# Power_Input.net
KiCad netlist of a schematic drawn in Altium Designer
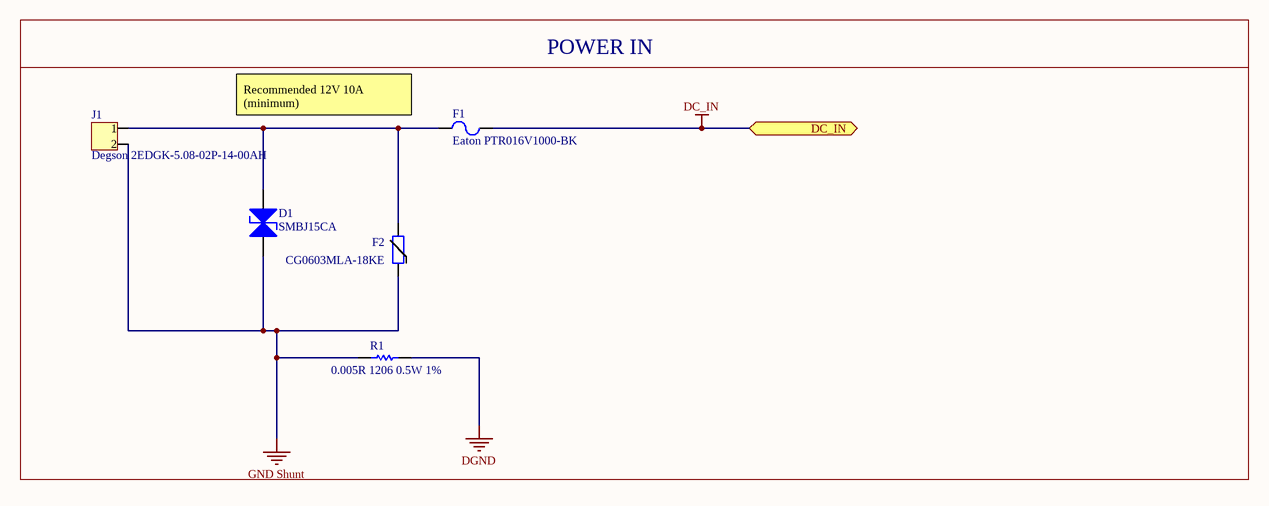
[diagram p0: Power_Input.SchDoc]

(export (version "E")
  (design (tool "Eeschema 10.0.6"))
  (components
    (comp (ref "D1")
      (value "SMBJ15CA")
      (footprint "PCB-acsqsz06h0bi34fqghyj-1")
      (description "SMBJ15 Series 24.4 V 600 W Bi-Directional Transient Voltage Suppressor-DO-214AA")
      (libsource (lib "CommunityVault") (part "SYM-f09b39914f642f5c-1"))
    )
    (comp (ref "F1")
      (value "Eaton PTR016V1000-BK")
      (footprint "PCB-m5opblue4hjll7k5rrhf-1")
      (description "PTC Resettable Fuse 10A(hold) 17A(trip) 16VDC 100A 3.6W 6s 0.004Ohm Radial 16.5 X 3.1 X 25.2mm Bag")
      (fields (field (name "MANUFACTURER PART NUMBER") "PTR016V1000-BK"))
      (libsource (lib "FavoritesLibrary") (part "SYM-fef837fa79fb213f-1"))
    )
    (comp (ref "F2")
      (value "CG0603MLA-18KE")
      (footprint "CAPC1608X60X35NL10T15")
      (description "Var MOV 14VAC 18VDC 30A 24.2V 0603 SMD Paper T/R Var MOV 14VAC 18VDC 30A 24.2V 0603 SMD Paper T/R")
      (libsource (lib "FavoritesLibrary") (part "SYM-234feae503b6fc88-1"))
    )
    (comp (ref "J1")
      (value "Degson 2EDGK-5.08-02P-14-00AH")
      (footprint "PCB-h4cyb3wxd4gf7j132tzl-1")
      (description "Terminal block, 5mm 2 Pos, through hole male.")
      (fields (field (name "MANUFACTURER PART NUMBER") "2EDGK-5.08-02P-14-00AH + 2EDGVC-5.08-02P"))
      (libsource (lib "CommunityVault") (part "CMP-7a42b7ee166ba585-1"))
    )
    (comp (ref "R1")
      (value "0.005R 1206 0.5W 1%")
      (footprint "CAPC3216X180X55ML20T25")
      (fields (field (name "MANUFACTURER PART NUMBER") "WSLP12065L000FEA") (field (name "POWER") "1W"))
      (libsource (lib "CommunityVault") (part "CMP-0abdc173b10ad57a-1"))
    )
  )
  (nets
    (net (code "1") (name "DC_IN") (class "Default")
      (node (ref "F1") (pin "2") (pinfunction "2_2") (pintype "passive"))
    )
    (net (code "2") (name "DGND") (class "Default")
      (node (ref "R1") (pin "1") (pinfunction "1_1") (pintype "passive"))
    )
    (net (code "3") (name "GND Shunt") (class "Default")
      (node (ref "D1") (pin "1") (pinfunction "A_1") (pintype "passive"))
      (node (ref "F2") (pin "1") (pinfunction "1_1") (pintype "passive"))
      (node (ref "J1") (pin "2") (pinfunction "2_2") (pintype "passive"))
      (node (ref "R1") (pin "2") (pinfunction "2_2") (pintype "passive"))
    )
    (net (code "4") (name "Net-(D1-K)") (class "Default")
      (node (ref "D1") (pin "2") (pinfunction "K_2") (pintype "passive"))
      (node (ref "F1") (pin "1") (pinfunction "1_1") (pintype "passive"))
      (node (ref "F2") (pin "2") (pinfunction "2_2") (pintype "passive"))
      (node (ref "J1") (pin "1") (pinfunction "1_1") (pintype "passive"))
    )
  )
)
